# Control.net
KiCad netlist of a schematic drawn in Altium Designer
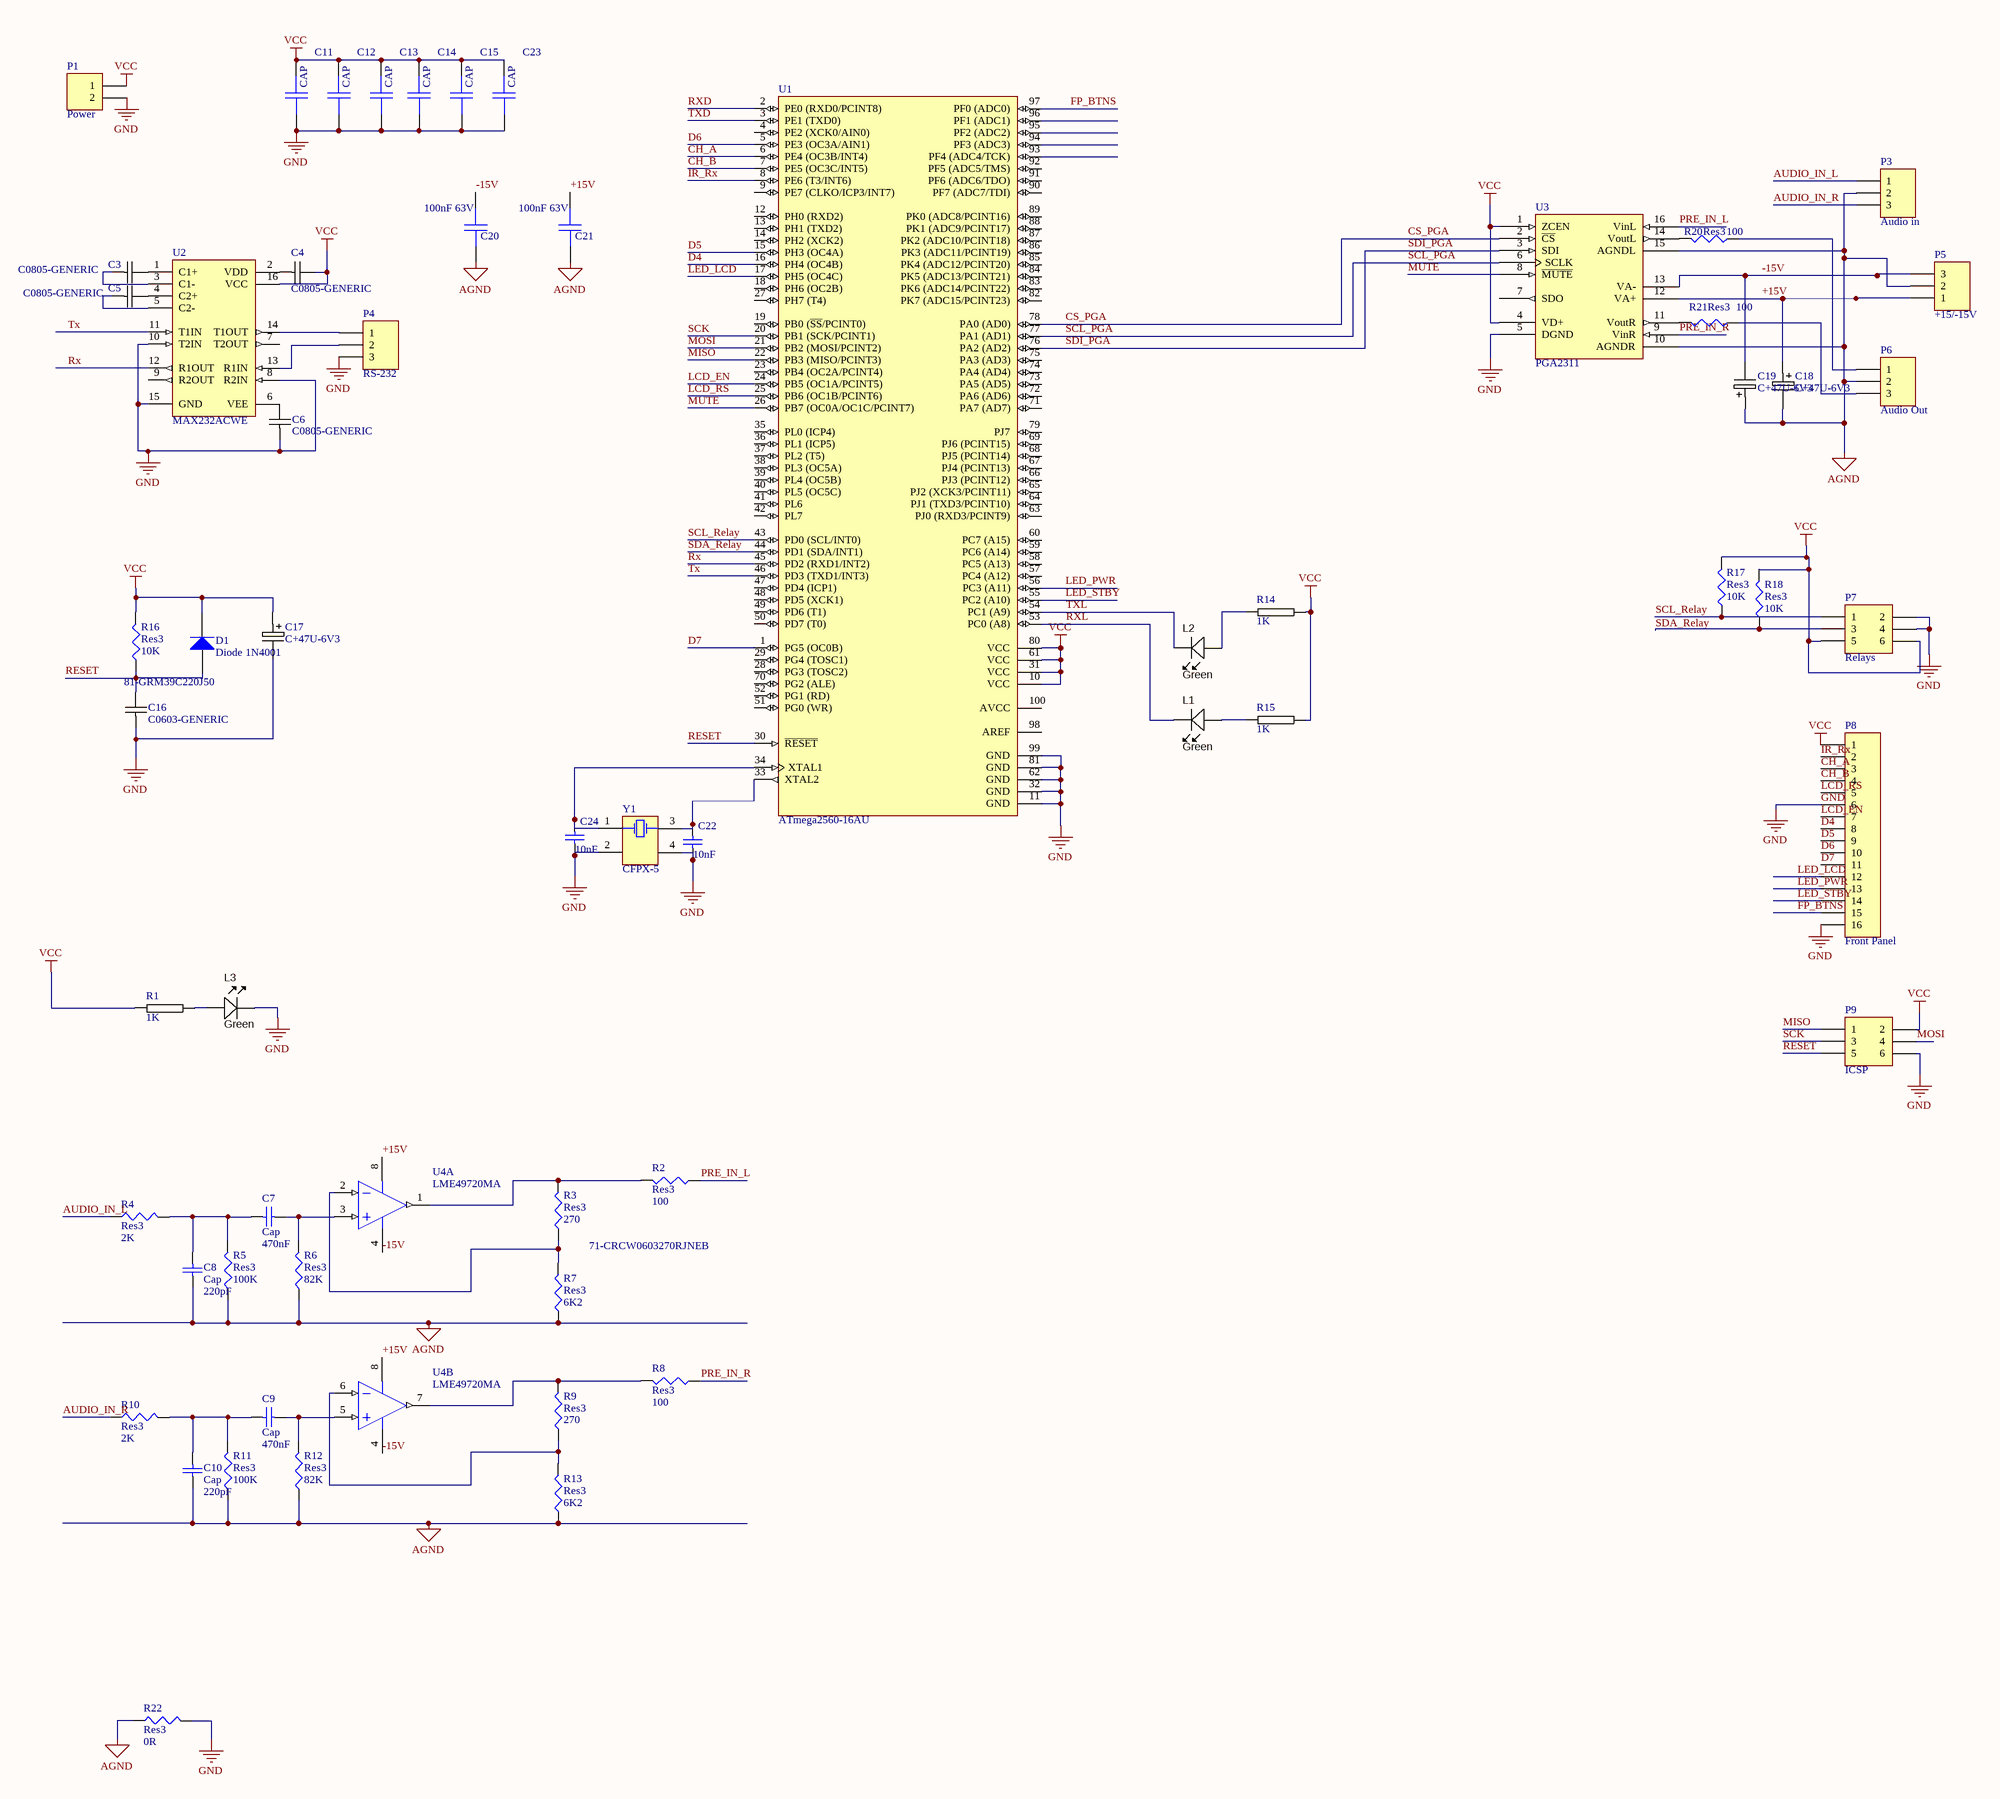
[diagram p0: Control.SchDoc]

(export (version "E")
  (design (tool "Eeschema 10.0.6"))
  (components
    (comp (ref "C3")
      (value "C0805-GENERIC")
      (footprint "0805C-GENERIC")
      (description "GENERIC CAPACITOR NON POLARISED0603")
      (libsource (lib "vh_altium_library") (part "C0805-GENERIC"))
    )
    (comp (ref "C4")
      (value "C0805-GENERIC")
      (footprint "0805C-GENERIC")
      (description "GENERIC CAPACITOR NON POLARISED0805")
      (libsource (lib "vh_altium_library") (part "C0805-GENERIC"))
    )
    (comp (ref "C5")
      (value "C0805-GENERIC")
      (footprint "0805C-GENERIC")
      (description "GENERIC CAPACITOR NON POLARISED0603")
      (libsource (lib "vh_altium_library") (part "C0805-GENERIC"))
    )
    (comp (ref "C6")
      (value "C0805-GENERIC")
      (footprint "0805C-GENERIC")
      (description "GENERIC CAPACITOR NON POLARISED0603")
      (libsource (lib "vh_altium_library") (part "C0805-GENERIC"))
    )
    (comp (ref "C7")
      (value "Cap")
      (footprint "CAPC3225X220N")
      (description "Capacitor")
      (fields (field (name "ALTIUM_VALUE") "470nF") (field (name "PUBLISHER") "Altium Limited"))
      (libsource (lib "Miscellaneous Devices") (part "Cap"))
    )
    (comp (ref "C8")
      (value "Cap")
      (footprint "CAPC2012X135N")
      (description "Capacitor")
      (fields (field (name "ALTIUM_VALUE") "220pF") (field (name "PUBLISHER") "Altium Limited"))
      (libsource (lib "Miscellaneous Devices") (part "Cap"))
    )
    (comp (ref "C9")
      (value "Cap")
      (footprint "CAPC3225X220N")
      (description "Capacitor")
      (fields (field (name "ALTIUM_VALUE") "470nF") (field (name "PUBLISHER") "Altium Limited"))
      (libsource (lib "Miscellaneous Devices") (part "Cap"))
    )
    (comp (ref "C10")
      (value "Cap")
      (footprint "CAPC2012X135N")
      (description "Capacitor")
      (fields (field (name "ALTIUM_VALUE") "220pF") (field (name "PUBLISHER") "Altium Limited"))
      (libsource (lib "Miscellaneous Devices") (part "Cap"))
    )
    (comp (ref "C11")
      (value "CAP")
      (footprint "CAPC2012")
      (description "Capacitor")
      (fields (field (name "PART NO.") "Not Part"))
      (libsource (lib "Components") (part "CAP"))
    )
    (comp (ref "C12")
      (value "CAP")
      (footprint "CAPC2012")
      (description "Capacitor")
      (fields (field (name "PART NO.") "Not Part"))
      (libsource (lib "Components") (part "CAP"))
    )
    (comp (ref "C13")
      (value "CAP")
      (footprint "CAPC2012")
      (description "Capacitor")
      (fields (field (name "PART NO.") "Not Part"))
      (libsource (lib "Components") (part "CAP"))
    )
    (comp (ref "C14")
      (value "CAP")
      (footprint "CAPC2012")
      (description "Capacitor")
      (fields (field (name "PART NO.") "Not Part"))
      (libsource (lib "Components") (part "CAP"))
    )
    (comp (ref "C15")
      (value "CAP")
      (footprint "CAPC2012")
      (description "Capacitor")
      (fields (field (name "PART NO.") "Not Part"))
      (libsource (lib "Components") (part "CAP"))
    )
    (comp (ref "C16")
      (value "C0603-GENERIC")
      (footprint "CAPC1608")
      (description "GENERIC CAPACITOR NON POLARISED 22pf")
      (fields
        (field (name "SUPPLIER PART NUMBER 1") "81-GRM39C220J50")
        (field (name "MANUFACTURER") "Murata Electronics")
        (field (name "MANUFACTURER PART NUMBER") "GRM1885C1H220JA01D")
      )
      (libsource (lib "vh_altium_library") (part "C0805-GENERIC"))
    )
    (comp (ref "C17")
      (value "C+47U-6V3")
      (footprint "PANACAP-C")
      (description "GENERIC CAPACITOR POLARISED")
      (libsource (lib "vh_altium_library") (part "C+47U-6V3"))
    )
    (comp (ref "C18")
      (value "C+47U-6V3")
      (footprint "PANACAP-C")
      (description "GENERIC CAPACITOR POLARISED")
      (libsource (lib "vh_altium_library") (part "C+47U-6V3"))
    )
    (comp (ref "C19")
      (value "C+47U-6V3")
      (footprint "PANACAP-C")
      (description "GENERIC CAPACITOR POLARISED")
      (libsource (lib "vh_altium_library") (part "C+47U-6V3"))
    )
    (comp (ref "C20")
      (value "100nF 63V")
      (footprint "CAPC3216B")
      (fields (field (name "PART NO.") "Not Part"))
      (libsource (lib "Components") (part "CAP"))
    )
    (comp (ref "C21")
      (value "100nF 63V")
      (footprint "CAPC3216B")
      (fields (field (name "PART NO.") "Not Part"))
      (libsource (lib "Components") (part "CAP"))
    )
    (comp (ref "C22")
      (value "10nF")
      (footprint "CAPC1005L")
      (description "Capacitor")
      (fields (field (name "PUBLISHER") "Altium Limited"))
      (libsource (lib "Miscellaneous Devices") (part "Cap"))
    )
    (comp (ref "C23")
      (value "CAP")
      (footprint "CAPC2012")
      (description "Capacitor")
      (fields (field (name "PART NO.") "Not Part"))
      (libsource (lib "Components") (part "CAP"))
    )
    (comp (ref "C24")
      (value "10nF")
      (footprint "CAPC1005L")
      (description "Capacitor")
      (fields (field (name "PUBLISHER") "Altium Limited"))
      (libsource (lib "Miscellaneous Devices") (part "Cap"))
    )
    (comp (ref "D1")
      (value "Diode 1N4001")
      (footprint "1206 Diode")
      (description "1 Amp General Purpose Rectifier")
      (fields (field (name "PUBLISHER") "Altium Limited"))
      (libsource (lib "Miscellaneous Devices") (part "Diode 1N4001"))
    )
    (comp (ref "L1")
      (value "~")
      (footprint "LED-0805-K")
      (description "LED, 0805 SMD, Green")
      (fields (field (name "COLOR") "Green"))
      (libsource (lib "PBL - Light Sources") (part "LED_SMD_Green_0805_6mcd"))
    )
    (comp (ref "L2")
      (value "~")
      (footprint "LED-0805-K")
      (description "LED, 0805 SMD, Green")
      (fields (field (name "COLOR") "Green"))
      (libsource (lib "PBL - Light Sources") (part "LED_SMD_Green_0805_6mcd"))
    )
    (comp (ref "L3")
      (value "~")
      (footprint "LED-0805-K")
      (description "LED, 0805 SMD, Green")
      (fields (field (name "COLOR") "Green"))
      (libsource (lib "PBL - Light Sources") (part "LED_SMD_Green_0805_6mcd"))
    )
    (comp (ref "P1")
      (value "Power")
      (footprint "PH_TERM_2")
      (description "Header, 2-Pin")
      (fields (field (name "PUBLISHER") "Altium Limited"))
      (libsource (lib "Miscellaneous Connectors") (part "Header 2"))
    )
    (comp (ref "P3")
      (value "Audio in")
      (footprint "PH_TERM_3")
      (description "Header, 3-Pin")
      (fields (field (name "PUBLISHER") "Altium Limited"))
      (libsource (lib "") (part "Header 3_1"))
    )
    (comp (ref "P4")
      (value "RS-232")
      (footprint "HDR1X3H")
      (description "Header, 3-Pin, Right Angle")
      (fields (field (name "PUBLISHER") "Altium Limited"))
      (libsource (lib "Miscellaneous Connectors") (part "Header 3H"))
    )
    (comp (ref "P5")
      (value "+15/-15V")
      (footprint "PH_TERM_3")
      (description "Header, 3-Pin")
      (fields (field (name "PUBLISHER") "Altium Limited"))
      (libsource (lib "Miscellaneous Connectors") (part "Header 3"))
    )
    (comp (ref "P6")
      (value "Audio Out")
      (footprint "PH_TERM_3")
      (description "Header, 3-Pin")
      (fields (field (name "PUBLISHER") "Altium Limited"))
      (libsource (lib "") (part "Header 3_1"))
    )
    (comp (ref "P7")
      (value "Relays")
      (footprint "HDR2X3H")
      (description "Header, 3-Pin, Dual row, Right Angle")
      (fields (field (name "PUBLISHER") "Altium Limited"))
      (libsource (lib "Miscellaneous Connectors") (part "Header 3X2H"))
    )
    (comp (ref "P8")
      (value "Front Panel")
      (footprint "IDC2.54-H16C")
      (description "Header, 16-Pin")
      (fields (field (name "PUBLISHER") "Altium Limited"))
      (libsource (lib "Miscellaneous Connectors") (part "Header 16"))
    )
    (comp (ref "P9")
      (value "ICSP")
      (footprint "HDR2X3")
      (description "Header, 3-Pin, Dual row")
      (fields (field (name "PUBLISHER") "Altium Limited"))
      (libsource (lib "Miscellaneous Connectors") (part "Header 3X2"))
    )
    (comp (ref "R1")
      (value "1K")
      (footprint "0805R-1K")
      (description "RESISTOR 0805 1/4 WATT THIN FILM")
      (libsource (lib "vh_altium_library") (part "0805R-1K"))
    )
    (comp (ref "R2")
      (value "Res3")
      (footprint "J1-0603")
      (description "Resistor")
      (fields (field (name "ALTIUM_VALUE") "100") (field (name "PUBLISHER") "Altium Limited"))
      (libsource (lib "Miscellaneous Devices") (part "Res3"))
    )
    (comp (ref "R3")
      (value "Res3")
      (footprint "J1-0603")
      (description "Resistor")
      (fields
        (field (name "ALTIUM_VALUE") "270")
        (field (name "SUPPLIER PART NUMBER 1") "71-CRCW0603270RJNEB")
        (field (name "PUBLISHER") "Altium Limited")
      )
      (libsource (lib "Miscellaneous Devices") (part "Res3"))
    )
    (comp (ref "R4")
      (value "Res3")
      (footprint "J1-0603")
      (description "Resistor")
      (fields (field (name "ALTIUM_VALUE") "2K") (field (name "PUBLISHER") "Altium Limited"))
      (libsource (lib "Miscellaneous Devices") (part "Res3"))
    )
    (comp (ref "R5")
      (value "Res3")
      (footprint "J1-0603")
      (description "Resistor")
      (fields (field (name "ALTIUM_VALUE") "100K") (field (name "PUBLISHER") "Altium Limited"))
      (libsource (lib "Miscellaneous Devices") (part "Res3"))
    )
    (comp (ref "R6")
      (value "Res3")
      (footprint "J1-0603")
      (description "Resistor")
      (fields (field (name "ALTIUM_VALUE") "82K") (field (name "PUBLISHER") "Altium Limited"))
      (libsource (lib "Miscellaneous Devices") (part "Res3"))
    )
    (comp (ref "R7")
      (value "Res3")
      (footprint "J1-0603")
      (description "Resistor")
      (fields (field (name "ALTIUM_VALUE") "6K2") (field (name "PUBLISHER") "Altium Limited"))
      (libsource (lib "Miscellaneous Devices") (part "Res3"))
    )
    (comp (ref "R8")
      (value "Res3")
      (footprint "J1-0603")
      (description "Resistor")
      (fields (field (name "ALTIUM_VALUE") "100") (field (name "PUBLISHER") "Altium Limited"))
      (libsource (lib "Miscellaneous Devices") (part "Res3"))
    )
    (comp (ref "R9")
      (value "Res3")
      (footprint "J1-0603")
      (description "Resistor")
      (fields (field (name "ALTIUM_VALUE") "270") (field (name "PUBLISHER") "Altium Limited"))
      (libsource (lib "Miscellaneous Devices") (part "Res3"))
    )
    (comp (ref "R10")
      (value "Res3")
      (footprint "J1-0603")
      (description "Resistor")
      (fields (field (name "ALTIUM_VALUE") "2K") (field (name "PUBLISHER") "Altium Limited"))
      (libsource (lib "Miscellaneous Devices") (part "Res3"))
    )
    (comp (ref "R11")
      (value "Res3")
      (footprint "J1-0603")
      (description "Resistor")
      (fields (field (name "ALTIUM_VALUE") "100K") (field (name "PUBLISHER") "Altium Limited"))
      (libsource (lib "Miscellaneous Devices") (part "Res3"))
    )
    (comp (ref "R12")
      (value "Res3")
      (footprint "J1-0603")
      (description "Resistor")
      (fields (field (name "ALTIUM_VALUE") "82K") (field (name "PUBLISHER") "Altium Limited"))
      (libsource (lib "Miscellaneous Devices") (part "Res3"))
    )
    (comp (ref "R13")
      (value "Res3")
      (footprint "J1-0603")
      (description "Resistor")
      (fields (field (name "ALTIUM_VALUE") "6K2") (field (name "PUBLISHER") "Altium Limited"))
      (libsource (lib "Miscellaneous Devices") (part "Res3"))
    )
    (comp (ref "R14")
      (value "1K")
      (footprint "0805R-1K")
      (description "RESISTOR 0805 1/4 WATT THIN FILM")
      (libsource (lib "vh_altium_library") (part "0805R-1K"))
    )
    (comp (ref "R15")
      (value "1K")
      (footprint "0805R-1K")
      (description "RESISTOR 0805 1/4 WATT THIN FILM")
      (libsource (lib "vh_altium_library") (part "0805R-1K"))
    )
    (comp (ref "R16")
      (value "Res3")
      (footprint "J1-0603")
      (description "Resistor")
      (fields (field (name "ALTIUM_VALUE") "10K") (field (name "PUBLISHER") "Altium Limited"))
      (libsource (lib "Miscellaneous Devices") (part "Res3"))
    )
    (comp (ref "R17")
      (value "Res3")
      (footprint "J1-0603")
      (description "Resistor")
      (fields (field (name "ALTIUM_VALUE") "10K") (field (name "PUBLISHER") "Altium Limited"))
      (libsource (lib "Miscellaneous Devices") (part "Res3"))
    )
    (comp (ref "R18")
      (value "Res3")
      (footprint "J1-0603")
      (description "Resistor")
      (fields (field (name "ALTIUM_VALUE") "10K") (field (name "PUBLISHER") "Altium Limited"))
      (libsource (lib "Miscellaneous Devices") (part "Res3"))
    )
    (comp (ref "R20")
      (value "Res3")
      (footprint "J1-0603")
      (description "Resistor")
      (fields (field (name "ALTIUM_VALUE") "100") (field (name "PUBLISHER") "Altium Limited"))
      (libsource (lib "Miscellaneous Devices") (part "Res3"))
    )
    (comp (ref "R21")
      (value "Res3")
      (footprint "J1-0603")
      (description "Resistor")
      (fields (field (name "ALTIUM_VALUE") "100") (field (name "PUBLISHER") "Altium Limited"))
      (libsource (lib "Miscellaneous Devices") (part "Res3"))
    )
    (comp (ref "R22")
      (value "Res3")
      (footprint "J1-0603")
      (description "Resistor")
      (fields (field (name "ALTIUM_VALUE") "0R") (field (name "PUBLISHER") "Altium Limited"))
      (libsource (lib "Miscellaneous Devices") (part "Res3"))
    )
    (comp (ref "U1")
      (value "ATmega2560-16AU")
      (footprint "100A_N")
      (fields (field (name "PUBLISHER") "Altium Limited"))
      (libsource (lib "Atmel Microcontroller 8-Bit megaAVR") (part "ATmega2560-16AU"))
    )
    (comp (ref "U2")
      (value "MAX232ACWE")
      (footprint "WSO16_N")
      (description "+5V Powered, Multi-Channel RS-232 Driver/Receiver")
      (fields (field (name "PUBLISHER") "Altium Limited"))
      (libsource (lib "Maxim Communication Transceiver") (part "MAX232ACWE"))
    )
    (comp (ref "U3")
      (value "PGA2311")
      (footprint "TI-DW16_L")
      (libsource (lib "Dales Custom Libs") (part "PGA2311"))
    )
    (comp (ref "U4")
      (value "LME49720MA")
      (footprint "M08A_N")
      (description "Dual High Performance, High Fidelity Audio Operational Amplifier, 8-pin Narrow SOIC")
      (fields
        (field (name "MANUFACTURER") "National Semiconductor")
        (field (name "PUBLISHER") "Altium Limited")
      )
      (libsource (lib "NSC Audio") (part "LME49720MA"))
    )
    (comp (ref "Y1")
      (value "CFPX-5")
      (footprint "CFPX-5")
      (description "Surface Mount Quartz Crystal")
      (fields (field (name "PUBLISHER") "Altium Limited"))
      (libsource (lib "C-MAC Crystal Oscillator") (part "CFPX-5"))
    )
  )
  (nets
    (net (code "1") (name "/+15V") (class "Default")
      (node (ref "C18") (pin "+") (pinfunction "+_+") (pintype "passive"))
      (node (ref "C21") (pin "1") (pinfunction "1_1") (pintype "passive"))
      (node (ref "P5") (pin "1") (pinfunction "1_1") (pintype "passive"))
      (node (ref "U3") (pin "12") (pinfunction "VA+_12") (pintype "power_in"))
      (node (ref "U4") (pin "8") (pinfunction "V+_8") (pintype "power_in"))
    )
    (net (code "2") (name "/-15V") (class "Default")
      (node (ref "C19") (pin "-") (pinfunction "-_-") (pintype "passive"))
      (node (ref "C20") (pin "1") (pinfunction "1_1") (pintype "passive"))
      (node (ref "P5") (pin "3") (pinfunction "3_3") (pintype "passive"))
      (node (ref "U3") (pin "13") (pinfunction "VA-_13") (pintype "power_in"))
      (node (ref "U4") (pin "4") (pinfunction "V-_4") (pintype "power_in"))
    )
    (net (code "3") (name "/AUDIO_IN_L") (class "Default")
      (node (ref "P3") (pin "1") (pinfunction "1_1") (pintype "passive"))
      (node (ref "R4") (pin "1") (pinfunction "1_1") (pintype "passive"))
    )
    (net (code "4") (name "/AUDIO_IN_R") (class "Default")
      (node (ref "P3") (pin "3") (pinfunction "3_3") (pintype "passive"))
      (node (ref "R10") (pin "1") (pinfunction "1_1") (pintype "passive"))
    )
    (net (code "5") (name "/CH_A") (class "Default")
      (node (ref "P8") (pin "3") (pinfunction "3_3") (pintype "passive"))
      (node (ref "U1") (pin "6") (pinfunction "PE4_(OC3B/INT4)_6") (pintype "bidirectional"))
    )
    (net (code "6") (name "/CH_B") (class "Default")
      (node (ref "P8") (pin "4") (pinfunction "4_4") (pintype "passive"))
      (node (ref "U1") (pin "7") (pinfunction "PE5_(OC3C/INT5)_7") (pintype "bidirectional"))
    )
    (net (code "7") (name "/CS_PGA") (class "Default")
      (node (ref "U1") (pin "78") (pinfunction "PA0_(AD0)_78") (pintype "bidirectional"))
      (node (ref "U3") (pin "2") (pinfunction "~{CS}_2") (pintype "input"))
    )
    (net (code "8") (name "/D4") (class "Default")
      (node (ref "P8") (pin "8") (pinfunction "8_8") (pintype "passive"))
      (node (ref "U1") (pin "16") (pinfunction "PH4_(OC4B)_16") (pintype "bidirectional"))
    )
    (net (code "9") (name "/D5") (class "Default")
      (node (ref "P8") (pin "9") (pinfunction "9_9") (pintype "passive"))
      (node (ref "U1") (pin "15") (pinfunction "PH3_(OC4A)_15") (pintype "bidirectional"))
    )
    (net (code "10") (name "/D6") (class "Default")
      (node (ref "P8") (pin "10") (pinfunction "10_10") (pintype "passive"))
      (node (ref "U1") (pin "5") (pinfunction "PE3_(OC3A/AIN1)_5") (pintype "bidirectional"))
    )
    (net (code "11") (name "/D7") (class "Default")
      (node (ref "P8") (pin "11") (pinfunction "11_11") (pintype "passive"))
      (node (ref "U1") (pin "1") (pinfunction "PG5_(OC0B)_1") (pintype "bidirectional"))
    )
    (net (code "12") (name "/FP_BTNS") (class "Default")
      (node (ref "P8") (pin "15") (pinfunction "15_15") (pintype "passive"))
      (node (ref "U1") (pin "97") (pinfunction "PF0_(ADC0)_97") (pintype "bidirectional"))
    )
    (net (code "13") (name "/IR_Rx") (class "Default")
      (node (ref "P8") (pin "2") (pinfunction "2_2") (pintype "passive"))
      (node (ref "U1") (pin "8") (pinfunction "PE6_(T3/INT6)_8") (pintype "bidirectional"))
    )
    (net (code "14") (name "/LCD_EN") (class "Default")
      (node (ref "P8") (pin "7") (pinfunction "7_7") (pintype "passive"))
      (node (ref "U1") (pin "24") (pinfunction "PB5_(OC1A/PCINT5)_24") (pintype "bidirectional"))
    )
    (net (code "15") (name "/LCD_RS") (class "Default")
      (node (ref "P8") (pin "5") (pinfunction "5_5") (pintype "passive"))
      (node (ref "U1") (pin "25") (pinfunction "PB6_(OC1B/PCINT6)_25") (pintype "bidirectional"))
    )
    (net (code "16") (name "/LED_LCD") (class "Default")
      (node (ref "P8") (pin "12") (pinfunction "12_12") (pintype "passive"))
      (node (ref "U1") (pin "17") (pinfunction "PH5_(OC4C)_17") (pintype "bidirectional"))
    )
    (net (code "17") (name "/LED_PWR") (class "Default")
      (node (ref "P8") (pin "13") (pinfunction "13_13") (pintype "passive"))
      (node (ref "U1") (pin "56") (pinfunction "PC3_(A11)_56") (pintype "bidirectional"))
    )
    (net (code "18") (name "/LED_STBY") (class "Default")
      (node (ref "P8") (pin "14") (pinfunction "14_14") (pintype "passive"))
      (node (ref "U1") (pin "55") (pinfunction "PC2_(A10)_55") (pintype "bidirectional"))
    )
    (net (code "19") (name "/MISO") (class "Default")
      (node (ref "P9") (pin "1") (pinfunction "1_1") (pintype "passive"))
      (node (ref "U1") (pin "22") (pinfunction "PB3_(MISO/PCINT3)_22") (pintype "bidirectional"))
    )
    (net (code "20") (name "/MOSI") (class "Default")
      (node (ref "P9") (pin "4") (pinfunction "4_4") (pintype "passive"))
      (node (ref "U1") (pin "21") (pinfunction "PB2_(MOSI/PCINT2)_21") (pintype "bidirectional"))
    )
    (net (code "21") (name "/MUTE") (class "Default")
      (node (ref "U1") (pin "26") (pinfunction "PB7_(OC0A/OC1C/PCINT7)_26") (pintype "bidirectional"))
      (node (ref "U3") (pin "8") (pinfunction "~{MUTE}_8") (pintype "input"))
    )
    (net (code "22") (name "/PRE_IN_L") (class "Default")
      (node (ref "R2") (pin "1") (pinfunction "1_1") (pintype "passive"))
      (node (ref "U3") (pin "16") (pinfunction "VinL_16") (pintype "input"))
    )
    (net (code "23") (name "/PRE_IN_R") (class "Default")
      (node (ref "R8") (pin "1") (pinfunction "1_1") (pintype "passive"))
      (node (ref "U3") (pin "9") (pinfunction "VinR_9") (pintype "input"))
    )
    (net (code "24") (name "/RESET") (class "Default")
      (node (ref "C16") (pin "2") (pintype "passive"))
      (node (ref "D1") (pin "1") (pinfunction "A_1") (pintype "passive"))
      (node (ref "P9") (pin "5") (pinfunction "5_5") (pintype "passive"))
      (node (ref "R16") (pin "1") (pinfunction "1_1") (pintype "passive"))
      (node (ref "U1") (pin "30") (pinfunction "~{RESET}_30") (pintype "input"))
    )
    (net (code "25") (name "/RXD") (class "Default")
      (node (ref "U1") (pin "2") (pinfunction "PE0_(RXD0/PCINT8)_2") (pintype "bidirectional"))
    )
    (net (code "26") (name "/RXL") (class "Default")
      (node (ref "L1") (pin "K") (pinfunction "K_K") (pintype "passive"))
      (node (ref "U1") (pin "53") (pinfunction "PC0_(A8)_53") (pintype "bidirectional"))
    )
    (net (code "27") (name "/Rx") (class "Default")
      (node (ref "U1") (pin "45") (pinfunction "PD2_(RXD1/INT2)_45") (pintype "bidirectional"))
      (node (ref "U2") (pin "12") (pinfunction "R1OUT_12") (pintype "output"))
    )
    (net (code "28") (name "/SCK") (class "Default")
      (node (ref "P9") (pin "3") (pinfunction "3_3") (pintype "passive"))
      (node (ref "U1") (pin "20") (pinfunction "PB1_(SCK/PCINT1)_20") (pintype "bidirectional"))
    )
    (net (code "29") (name "/SCL_PGA") (class "Default")
      (node (ref "U1") (pin "77") (pinfunction "PA1_(AD1)_77") (pintype "bidirectional"))
      (node (ref "U3") (pin "6") (pinfunction "SCLK_6") (pintype "passive"))
    )
    (net (code "30") (name "/SCL_Relay") (class "Default")
      (node (ref "P7") (pin "1") (pinfunction "1_1") (pintype "passive"))
      (node (ref "R17") (pin "1") (pinfunction "1_1") (pintype "passive"))
      (node (ref "U1") (pin "43") (pinfunction "PD0_(SCL/INT0)_43") (pintype "bidirectional"))
    )
    (net (code "31") (name "/SDA_Relay") (class "Default")
      (node (ref "P7") (pin "3") (pinfunction "3_3") (pintype "passive"))
      (node (ref "R18") (pin "1") (pinfunction "1_1") (pintype "passive"))
      (node (ref "U1") (pin "44") (pinfunction "PD1_(SDA/INT1)_44") (pintype "bidirectional"))
    )
    (net (code "32") (name "/SDI_PGA") (class "Default")
      (node (ref "U1") (pin "76") (pinfunction "PA2_(AD2)_76") (pintype "bidirectional"))
      (node (ref "U3") (pin "3") (pinfunction "SDI_3") (pintype "input"))
    )
    (net (code "33") (name "/TXD") (class "Default")
      (node (ref "U1") (pin "3") (pinfunction "PE1_(TXD0)_3") (pintype "bidirectional"))
    )
    (net (code "34") (name "/TXL") (class "Default")
      (node (ref "L2") (pin "K") (pinfunction "K_K") (pintype "passive"))
      (node (ref "U1") (pin "54") (pinfunction "PC1_(A9)_54") (pintype "bidirectional"))
    )
    (net (code "35") (name "/Tx") (class "Default")
      (node (ref "U1") (pin "46") (pinfunction "PD3_(TXD1/INT3)_46") (pintype "bidirectional"))
      (node (ref "U2") (pin "11") (pinfunction "T1IN_11") (pintype "input"))
    )
    (net (code "36") (name "AGND") (class "Default")
      (node (ref "C10") (pin "2") (pinfunction "2_2") (pintype "passive"))
      (node (ref "C18") (pin "-") (pinfunction "-_-") (pintype "passive"))
      (node (ref "C19") (pin "+") (pinfunction "+_+") (pintype "passive"))
      (node (ref "C20") (pin "2") (pinfunction "2_2") (pintype "passive"))
      (node (ref "C21") (pin "2") (pinfunction "2_2") (pintype "passive"))
      (node (ref "C8") (pin "1") (pinfunction "1_1") (pintype "passive"))
      (node (ref "P3") (pin "2") (pinfunction "2_2") (pintype "passive"))
      (node (ref "P5") (pin "2") (pinfunction "2_2") (pintype "passive"))
      (node (ref "P6") (pin "2") (pinfunction "2_2") (pintype "passive"))
      (node (ref "R11") (pin "1") (pinfunction "1_1") (pintype "passive"))
      (node (ref "R12") (pin "1") (pinfunction "1_1") (pintype "passive"))
      (node (ref "R13") (pin "1") (pinfunction "1_1") (pintype "passive"))
      (node (ref "R22") (pin "1") (pinfunction "1_1") (pintype "passive"))
      (node (ref "R5") (pin "1") (pinfunction "1_1") (pintype "passive"))
      (node (ref "R6") (pin "1") (pinfunction "1_1") (pintype "passive"))
      (node (ref "R7") (pin "1") (pinfunction "1_1") (pintype "passive"))
      (node (ref "U3") (pin "10") (pinfunction "AGNDR_10") (pintype "power_in"))
      (node (ref "U3") (pin "15") (pinfunction "AGNDL_15") (pintype "power_in"))
    )
    (net (code "37") (name "GND") (class "Default")
      (node (ref "C11") (pin "2") (pinfunction "2_2") (pintype "passive"))
      (node (ref "C12") (pin "2") (pinfunction "2_2") (pintype "passive"))
      (node (ref "C13") (pin "2") (pinfunction "2_2") (pintype "passive"))
      (node (ref "C14") (pin "2") (pinfunction "2_2") (pintype "passive"))
      (node (ref "C15") (pin "2") (pinfunction "2_2") (pintype "passive"))
      (node (ref "C16") (pin "1") (pintype "passive"))
      (node (ref "C17") (pin "-") (pinfunction "-_-") (pintype "passive"))
      (node (ref "C22") (pin "1") (pinfunction "1_1") (pintype "passive"))
      (node (ref "C23") (pin "2") (pinfunction "2_2") (pintype "passive"))
      (node (ref "C24") (pin "1") (pinfunction "1_1") (pintype "passive"))
      (node (ref "C6") (pin "1") (pintype "passive"))
      (node (ref "L3") (pin "K") (pinfunction "K_K") (pintype "passive"))
      (node (ref "P1") (pin "2") (pinfunction "2_2") (pintype "passive"))
      (node (ref "P4") (pin "3") (pinfunction "3_3") (pintype "passive"))
      (node (ref "P7") (pin "2") (pinfunction "2_2") (pintype "passive"))
      (node (ref "P7") (pin "4") (pinfunction "4_4") (pintype "passive"))
      (node (ref "P8") (pin "16") (pinfunction "16_16") (pintype "passive"))
      (node (ref "P8") (pin "6") (pinfunction "6_6") (pintype "passive"))
      (node (ref "P9") (pin "6") (pinfunction "6_6") (pintype "passive"))
      (node (ref "R22") (pin "2") (pinfunction "2_2") (pintype "passive"))
      (node (ref "U1") (pin "11") (pinfunction "GND_11") (pintype "power_in"))
      (node (ref "U1") (pin "32") (pinfunction "GND_32") (pintype "power_in"))
      (node (ref "U1") (pin "62") (pinfunction "GND_62") (pintype "power_in"))
      (node (ref "U1") (pin "81") (pinfunction "GND_81") (pintype "power_in"))
      (node (ref "U1") (pin "99") (pinfunction "GND_99") (pintype "power_in"))
      (node (ref "U2") (pin "10") (pinfunction "T2IN_10") (pintype "input"))
      (node (ref "U2") (pin "15") (pinfunction "GND_15") (pintype "power_in"))
      (node (ref "U2") (pin "8") (pinfunction "R2IN_8") (pintype "input"))
      (node (ref "U3") (pin "5") (pinfunction "DGND_5") (pintype "power_in"))
      (node (ref "Y1") (pin "2") (pinfunction "NC_2") (pintype "passive"))
      (node (ref "Y1") (pin "4") (pinfunction "NC_4") (pintype "passive"))
    )
    (net (code "38") (name "Net-(C7-Pad1)") (class "Default")
      (node (ref "C7") (pin "1") (pinfunction "1_1") (pintype "passive"))
      (node (ref "R6") (pin "2") (pinfunction "2_2") (pintype "passive"))
      (node (ref "U4") (pin "3") (pinfunction "IN_A_3") (pintype "input"))
    )
    (net (code "39") (name "Net-(C7-Pad2)") (class "Default")
      (node (ref "C7") (pin "2") (pinfunction "2_2") (pintype "passive"))
      (node (ref "C8") (pin "2") (pinfunction "2_2") (pintype "passive"))
      (node (ref "R4") (pin "2") (pinfunction "2_2") (pintype "passive"))
      (node (ref "R5") (pin "2") (pinfunction "2_2") (pintype "passive"))
    )
    (net (code "40") (name "Net-(C9-Pad2)") (class "Default")
      (node (ref "C9") (pin "2") (pinfunction "2_2") (pintype "passive"))
      (node (ref "R12") (pin "2") (pinfunction "2_2") (pintype "passive"))
      (node (ref "U4") (pin "5") (pinfunction "IN_B_5") (pintype "input"))
    )
    (net (code "41") (name "Net-(C10-Pad1)") (class "Default")
      (node (ref "C10") (pin "1") (pinfunction "1_1") (pintype "passive"))
      (node (ref "C9") (pin "1") (pinfunction "1_1") (pintype "passive"))
      (node (ref "R10") (pin "2") (pinfunction "2_2") (pintype "passive"))
      (node (ref "R11") (pin "2") (pinfunction "2_2") (pintype "passive"))
    )
    (net (code "42") (name "Net-(L1-PadA)") (class "Default")
      (node (ref "L1") (pin "A") (pinfunction "A_A") (pintype "passive"))
      (node (ref "R15") (pin "1") (pintype "passive"))
    )
    (net (code "43") (name "Net-(L2-PadA)") (class "Default")
      (node (ref "L2") (pin "A") (pinfunction "A_A") (pintype "passive"))
      (node (ref "R14") (pin "1") (pintype "passive"))
    )
    (net (code "44") (name "Net-(L3-PadA)") (class "Default")
      (node (ref "L3") (pin "A") (pinfunction "A_A") (pintype "passive"))
      (node (ref "R1") (pin "2") (pintype "passive"))
    )
    (net (code "45") (name "Net-(P6-Pad1)") (class "Default")
      (node (ref "P6") (pin "1") (pinfunction "1_1") (pintype "passive"))
      (node (ref "R20") (pin "1") (pinfunction "1_1") (pintype "passive"))
    )
    (net (code "46") (name "Net-(P6-Pad3)") (class "Default")
      (node (ref "P6") (pin "3") (pinfunction "3_3") (pintype "passive"))
      (node (ref "R21") (pin "1") (pinfunction "1_1") (pintype "passive"))
    )
    (net (code "47") (name "Net-(R3-Pad1)") (class "Default")
      (node (ref "R3") (pin "1") (pinfunction "1_1") (pintype "passive"))
      (node (ref "R7") (pin "2") (pinfunction "2_2") (pintype "passive"))
      (node (ref "U4") (pin "2") (pinfunction "IN_A_2") (pintype "input"))
    )
    (net (code "48") (name "Net-(R13-Pad2)") (class "Default")
      (node (ref "R13") (pin "2") (pinfunction "2_2") (pintype "passive"))
      (node (ref "R9") (pin "1") (pinfunction "1_1") (pintype "passive"))
      (node (ref "U4") (pin "6") (pinfunction "IN_B_6") (pintype "input"))
    )
    (net (code "49") (name "Net-(U1-XTAL1)") (class "Default")
      (node (ref "C24") (pin "2") (pinfunction "2_2") (pintype "passive"))
      (node (ref "U1") (pin "34") (pinfunction "XTAL1_34") (pintype "input"))
      (node (ref "Y1") (pin "1") (pinfunction "OSC1_1") (pintype "passive"))
    )
    (net (code "50") (name "Net-(U1-XTAL2)") (class "Default")
      (node (ref "C22") (pin "2") (pinfunction "2_2") (pintype "passive"))
      (node (ref "U1") (pin "33") (pinfunction "XTAL2_33") (pintype "output"))
      (node (ref "Y1") (pin "3") (pinfunction "OSC2_3") (pintype "passive"))
    )
    (net (code "51") (name "Net-(U2-C1+)") (class "Default")
      (node (ref "C3") (pin "2") (pintype "passive"))
      (node (ref "U2") (pin "1") (pinfunction "C1+_1") (pintype "passive"))
    )
    (net (code "52") (name "Net-(U2-C1-)") (class "Default")
      (node (ref "C3") (pin "1") (pintype "passive"))
      (node (ref "U2") (pin "3") (pinfunction "C1-_3") (pintype "passive"))
    )
    (net (code "53") (name "Net-(U2-C2+)") (class "Default")
      (node (ref "C5") (pin "2") (pintype "passive"))
      (node (ref "U2") (pin "4") (pinfunction "C2+_4") (pintype "passive"))
    )
    (net (code "54") (name "Net-(U2-C2-)") (class "Default")
      (node (ref "C5") (pin "1") (pintype "passive"))
      (node (ref "U2") (pin "5") (pinfunction "C2-_5") (pintype "passive"))
    )
    (net (code "55") (name "Net-(U2-R1IN)") (class "Default")
      (node (ref "P4") (pin "2") (pinfunction "2_2") (pintype "passive"))
      (node (ref "U2") (pin "13") (pinfunction "R1IN_13") (pintype "input"))
    )
    (net (code "56") (name "Net-(U2-T1OUT)") (class "Default")
      (node (ref "P4") (pin "1") (pinfunction "1_1") (pintype "passive"))
      (node (ref "U2") (pin "14") (pinfunction "T1OUT_14") (pintype "output"))
    )
    (net (code "57") (name "Net-(U2-VDD)") (class "Default")
      (node (ref "C4") (pin "1") (pintype "passive"))
      (node (ref "U2") (pin "2") (pinfunction "VDD_2") (pintype "power_in"))
    )
    (net (code "58") (name "Net-(U2-VEE)") (class "Default")
      (node (ref "C6") (pin "2") (pintype "passive"))
      (node (ref "U2") (pin "6") (pinfunction "VEE_6") (pintype "power_in"))
    )
    (net (code "59") (name "Net-(U3-VoutL)") (class "Default")
      (node (ref "R20") (pin "2") (pinfunction "2_2") (pintype "passive"))
      (node (ref "U3") (pin "14") (pinfunction "VoutL_14") (pintype "output"))
    )
    (net (code "60") (name "Net-(U3-VoutR)") (class "Default")
      (node (ref "R21") (pin "2") (pinfunction "2_2") (pintype "passive"))
      (node (ref "U3") (pin "11") (pinfunction "VoutR_11") (pintype "output"))
    )
    (net (code "61") (name "Net-(U4A-OUT_A)") (class "Default")
      (node (ref "R2") (pin "2") (pinfunction "2_2") (pintype "passive"))
      (node (ref "R3") (pin "2") (pinfunction "2_2") (pintype "passive"))
      (node (ref "U4") (pin "1") (pinfunction "OUT_A_1") (pintype "output"))
    )
    (net (code "62") (name "Net-(U4B-OUT_B)") (class "Default")
      (node (ref "R8") (pin "2") (pinfunction "2_2") (pintype "passive"))
      (node (ref "R9") (pin "2") (pinfunction "2_2") (pintype "passive"))
      (node (ref "U4") (pin "7") (pinfunction "OUT_B_7") (pintype "output"))
    )
    (net (code "63") (name "VCC") (class "Default")
      (node (ref "C11") (pin "1") (pinfunction "1_1") (pintype "passive"))
      (node (ref "C12") (pin "1") (pinfunction "1_1") (pintype "passive"))
      (node (ref "C13") (pin "1") (pinfunction "1_1") (pintype "passive"))
      (node (ref "C14") (pin "1") (pinfunction "1_1") (pintype "passive"))
      (node (ref "C15") (pin "1") (pinfunction "1_1") (pintype "passive"))
      (node (ref "C17") (pin "+") (pinfunction "+_+") (pintype "passive"))
      (node (ref "C23") (pin "1") (pinfunction "1_1") (pintype "passive"))
      (node (ref "C4") (pin "2") (pintype "passive"))
      (node (ref "D1") (pin "2") (pinfunction "K_2") (pintype "passive"))
      (node (ref "P1") (pin "1") (pinfunction "1_1") (pintype "passive"))
      (node (ref "P7") (pin "5") (pinfunction "5_5") (pintype "passive"))
      (node (ref "P7") (pin "6") (pinfunction "6_6") (pintype "passive"))
      (node (ref "P8") (pin "1") (pinfunction "1_1") (pintype "passive"))
      (node (ref "P9") (pin "2") (pinfunction "2_2") (pintype "passive"))
      (node (ref "R1") (pin "1") (pintype "passive"))
      (node (ref "R14") (pin "2") (pintype "passive"))
      (node (ref "R15") (pin "2") (pintype "passive"))
      (node (ref "R16") (pin "2") (pinfunction "2_2") (pintype "passive"))
      (node (ref "R17") (pin "2") (pinfunction "2_2") (pintype "passive"))
      (node (ref "R18") (pin "2") (pinfunction "2_2") (pintype "passive"))
      (node (ref "U1") (pin "10") (pinfunction "VCC_10") (pintype "power_in"))
      (node (ref "U1") (pin "31") (pinfunction "VCC_31") (pintype "power_in"))
      (node (ref "U1") (pin "61") (pinfunction "VCC_61") (pintype "power_in"))
      (node (ref "U1") (pin "80") (pinfunction "VCC_80") (pintype "power_in"))
      (node (ref "U2") (pin "16") (pinfunction "VCC_16") (pintype "power_in"))
      (node (ref "U3") (pin "1") (pinfunction "ZCEN_1") (pintype "input"))
      (node (ref "U3") (pin "4") (pinfunction "VD+_4") (pintype "power_in"))
    )
    (net (code "64") (name "unconnected-(U1-AREF-Pad98)") (class "Default")
      (node (ref "U1") (pin "98") (pinfunction "AREF_98") (pintype "power_in"))
    )
    (net (code "65") (name "unconnected-(U1-AVCC-Pad100)") (class "Default")
      (node (ref "U1") (pin "100") (pinfunction "AVCC_100") (pintype "power_in"))
    )
    (net (code "66") (name "unconnected-(U1-PA3_(AD3)-Pad75)") (class "Default")
      (node (ref "U1") (pin "75") (pinfunction "PA3_(AD3)_75") (pintype "bidirectional"))
    )
    (net (code "67") (name "unconnected-(U1-PA4_(AD4)-Pad74)") (class "Default")
      (node (ref "U1") (pin "74") (pinfunction "PA4_(AD4)_74") (pintype "bidirectional"))
    )
    (net (code "68") (name "unconnected-(U1-PA5_(AD5)-Pad73)") (class "Default")
      (node (ref "U1") (pin "73") (pinfunction "PA5_(AD5)_73") (pintype "bidirectional"))
    )
    (net (code "69") (name "unconnected-(U1-PA6_(AD6)-Pad72)") (class "Default")
      (node (ref "U1") (pin "72") (pinfunction "PA6_(AD6)_72") (pintype "bidirectional"))
    )
    (net (code "70") (name "unconnected-(U1-PA7_(AD7)-Pad71)") (class "Default")
      (node (ref "U1") (pin "71") (pinfunction "PA7_(AD7)_71") (pintype "bidirectional"))
    )
    (net (code "71") (name "unconnected-(U1-PB0_(~{SS}{slash}PCINT0)-Pad19)") (class "Default")
      (node (ref "U1") (pin "19") (pinfunction "PB0_(~{SS}/PCINT0)_19") (pintype "bidirectional"))
    )
    (net (code "72") (name "unconnected-(U1-PB4_(OC2A{slash}PCINT4)-Pad23)") (class "Default")
      (node (ref "U1") (pin "23") (pinfunction "PB4_(OC2A/PCINT4)_23") (pintype "bidirectional"))
    )
    (net (code "73") (name "unconnected-(U1-PC4_(A12)-Pad57)") (class "Default")
      (node (ref "U1") (pin "57") (pinfunction "PC4_(A12)_57") (pintype "bidirectional"))
    )
    (net (code "74") (name "unconnected-(U1-PC5_(A13)-Pad58)") (class "Default")
      (node (ref "U1") (pin "58") (pinfunction "PC5_(A13)_58") (pintype "bidirectional"))
    )
    (net (code "75") (name "unconnected-(U1-PC6_(A14)-Pad59)") (class "Default")
      (node (ref "U1") (pin "59") (pinfunction "PC6_(A14)_59") (pintype "bidirectional"))
    )
    (net (code "76") (name "unconnected-(U1-PC7_(A15)-Pad60)") (class "Default")
      (node (ref "U1") (pin "60") (pinfunction "PC7_(A15)_60") (pintype "bidirectional"))
    )
    (net (code "77") (name "unconnected-(U1-PD4_(ICP1)-Pad47)") (class "Default")
      (node (ref "U1") (pin "47") (pinfunction "PD4_(ICP1)_47") (pintype "bidirectional"))
    )
    (net (code "78") (name "unconnected-(U1-PD5_(XCK1)-Pad48)") (class "Default")
      (node (ref "U1") (pin "48") (pinfunction "PD5_(XCK1)_48") (pintype "bidirectional"))
    )
    (net (code "79") (name "unconnected-(U1-PD6_(T1)-Pad49)") (class "Default")
      (node (ref "U1") (pin "49") (pinfunction "PD6_(T1)_49") (pintype "bidirectional"))
    )
    (net (code "80") (name "unconnected-(U1-PD7_(T0)-Pad50)") (class "Default")
      (node (ref "U1") (pin "50") (pinfunction "PD7_(T0)_50") (pintype "bidirectional"))
    )
    (net (code "81") (name "unconnected-(U1-PE2_(XCK0{slash}AIN0)-Pad4)") (class "Default")
      (node (ref "U1") (pin "4") (pinfunction "PE2_(XCK0/AIN0)_4") (pintype "bidirectional"))
    )
    (net (code "82") (name "unconnected-(U1-PE7_(CLKO{slash}ICP3{slash}INT7)-Pad9)") (class "Default")
      (node (ref "U1") (pin "9") (pinfunction "PE7_(CLKO/ICP3/INT7)_9") (pintype "bidirectional"))
    )
    (net (code "83") (name "unconnected-(U1-PF1_(ADC1)-Pad96)") (class "Default")
      (node (ref "U1") (pin "96") (pinfunction "PF1_(ADC1)_96") (pintype "bidirectional"))
    )
    (net (code "84") (name "unconnected-(U1-PF2_(ADC2)-Pad95)") (class "Default")
      (node (ref "U1") (pin "95") (pinfunction "PF2_(ADC2)_95") (pintype "bidirectional"))
    )
    (net (code "85") (name "unconnected-(U1-PF3_(ADC3)-Pad94)") (class "Default")
      (node (ref "U1") (pin "94") (pinfunction "PF3_(ADC3)_94") (pintype "bidirectional"))
    )
    (net (code "86") (name "unconnected-(U1-PF4_(ADC4{slash}TCK)-Pad93)") (class "Default")
      (node (ref "U1") (pin "93") (pinfunction "PF4_(ADC4/TCK)_93") (pintype "bidirectional"))
    )
    (net (code "87") (name "unconnected-(U1-PF5_(ADC5{slash}TMS)-Pad92)") (class "Default")
      (node (ref "U1") (pin "92") (pinfunction "PF5_(ADC5/TMS)_92") (pintype "bidirectional"))
    )
    (net (code "88") (name "unconnected-(U1-PF6_(ADC6{slash}TDO)-Pad91)") (class "Default")
      (node (ref "U1") (pin "91") (pinfunction "PF6_(ADC6/TDO)_91") (pintype "bidirectional"))
    )
    (net (code "89") (name "unconnected-(U1-PF7_(ADC7{slash}TDI)-Pad90)") (class "Default")
      (node (ref "U1") (pin "90") (pinfunction "PF7_(ADC7/TDI)_90") (pintype "bidirectional"))
    )
    (net (code "90") (name "unconnected-(U1-PG0_(WR)-Pad51)") (class "Default")
      (node (ref "U1") (pin "51") (pinfunction "PG0_(WR)_51") (pintype "bidirectional"))
    )
    (net (code "91") (name "unconnected-(U1-PG1_(RD)-Pad52)") (class "Default")
      (node (ref "U1") (pin "52") (pinfunction "PG1_(RD)_52") (pintype "bidirectional"))
    )
    (net (code "92") (name "unconnected-(U1-PG2_(ALE)-Pad70)") (class "Default")
      (node (ref "U1") (pin "70") (pinfunction "PG2_(ALE)_70") (pintype "bidirectional"))
    )
    (net (code "93") (name "unconnected-(U1-PG3_(TOSC2)-Pad28)") (class "Default")
      (node (ref "U1") (pin "28") (pinfunction "PG3_(TOSC2)_28") (pintype "bidirectional"))
    )
    (net (code "94") (name "unconnected-(U1-PG4_(TOSC1)-Pad29)") (class "Default")
      (node (ref "U1") (pin "29") (pinfunction "PG4_(TOSC1)_29") (pintype "bidirectional"))
    )
    (net (code "95") (name "unconnected-(U1-PH0_(RXD2)-Pad12)") (class "Default")
      (node (ref "U1") (pin "12") (pinfunction "PH0_(RXD2)_12") (pintype "bidirectional"))
    )
    (net (code "96") (name "unconnected-(U1-PH1_(TXD2)-Pad13)") (class "Default")
      (node (ref "U1") (pin "13") (pinfunction "PH1_(TXD2)_13") (pintype "bidirectional"))
    )
    (net (code "97") (name "unconnected-(U1-PH2_(XCK2)-Pad14)") (class "Default")
      (node (ref "U1") (pin "14") (pinfunction "PH2_(XCK2)_14") (pintype "bidirectional"))
    )
    (net (code "98") (name "unconnected-(U1-PH6_(OC2B)-Pad18)") (class "Default")
      (node (ref "U1") (pin "18") (pinfunction "PH6_(OC2B)_18") (pintype "bidirectional"))
    )
    (net (code "99") (name "unconnected-(U1-PH7_(T4)-Pad27)") (class "Default")
      (node (ref "U1") (pin "27") (pinfunction "PH7_(T4)_27") (pintype "bidirectional"))
    )
    (net (code "100") (name "unconnected-(U1-PJ0_(RXD3{slash}PCINT9)-Pad63)") (class "Default")
      (node (ref "U1") (pin "63") (pinfunction "PJ0_(RXD3/PCINT9)_63") (pintype "bidirectional"))
    )
    (net (code "101") (name "unconnected-(U1-PJ1_(TXD3{slash}PCINT10)-Pad64)") (class "Default")
      (node (ref "U1") (pin "64") (pinfunction "PJ1_(TXD3/PCINT10)_64") (pintype "bidirectional"))
    )
    (net (code "102") (name "unconnected-(U1-PJ2_(XCK3{slash}PCINT11)-Pad65)") (class "Default")
      (node (ref "U1") (pin "65") (pinfunction "PJ2_(XCK3/PCINT11)_65") (pintype "bidirectional"))
    )
    (net (code "103") (name "unconnected-(U1-PJ3_(PCINT12)-Pad66)") (class "Default")
      (node (ref "U1") (pin "66") (pinfunction "PJ3_(PCINT12)_66") (pintype "bidirectional"))
    )
    (net (code "104") (name "unconnected-(U1-PJ4_(PCINT13)-Pad67)") (class "Default")
      (node (ref "U1") (pin "67") (pinfunction "PJ4_(PCINT13)_67") (pintype "bidirectional"))
    )
    (net (code "105") (name "unconnected-(U1-PJ5_(PCINT14)-Pad68)") (class "Default")
      (node (ref "U1") (pin "68") (pinfunction "PJ5_(PCINT14)_68") (pintype "bidirectional"))
    )
    (net (code "106") (name "unconnected-(U1-PJ6_(PCINT15)-Pad69)") (class "Default")
      (node (ref "U1") (pin "69") (pinfunction "PJ6_(PCINT15)_69") (pintype "bidirectional"))
    )
    (net (code "107") (name "unconnected-(U1-PJ7-Pad79)") (class "Default")
      (node (ref "U1") (pin "79") (pinfunction "PJ7_79") (pintype "bidirectional"))
    )
    (net (code "108") (name "unconnected-(U1-PK0_(ADC8{slash}PCINT16)-Pad89)") (class "Default")
      (node (ref "U1") (pin "89") (pinfunction "PK0_(ADC8/PCINT16)_89") (pintype "bidirectional"))
    )
    (net (code "109") (name "unconnected-(U1-PK1_(ADC9{slash}PCINT17)-Pad88)") (class "Default")
      (node (ref "U1") (pin "88") (pinfunction "PK1_(ADC9/PCINT17)_88") (pintype "bidirectional"))
    )
    (net (code "110") (name "unconnected-(U1-PK2_(ADC10{slash}PCINT18)-Pad87)") (class "Default")
      (node (ref "U1") (pin "87") (pinfunction "PK2_(ADC10/PCINT18)_87") (pintype "bidirectional"))
    )
    (net (code "111") (name "unconnected-(U1-PK3_(ADC11{slash}PCINT19)-Pad86)") (class "Default")
      (node (ref "U1") (pin "86") (pinfunction "PK3_(ADC11/PCINT19)_86") (pintype "bidirectional"))
    )
    (net (code "112") (name "unconnected-(U1-PK4_(ADC12{slash}PCINT20)-Pad85)") (class "Default")
      (node (ref "U1") (pin "85") (pinfunction "PK4_(ADC12/PCINT20)_85") (pintype "bidirectional"))
    )
    (net (code "113") (name "unconnected-(U1-PK5_(ADC13{slash}PCINT21)-Pad84)") (class "Default")
      (node (ref "U1") (pin "84") (pinfunction "PK5_(ADC13/PCINT21)_84") (pintype "bidirectional"))
    )
    (net (code "114") (name "unconnected-(U1-PK6_(ADC14{slash}PCINT22)-Pad83)") (class "Default")
      (node (ref "U1") (pin "83") (pinfunction "PK6_(ADC14/PCINT22)_83") (pintype "bidirectional"))
    )
    (net (code "115") (name "unconnected-(U1-PK7_(ADC15{slash}PCINT23)-Pad82)") (class "Default")
      (node (ref "U1") (pin "82") (pinfunction "PK7_(ADC15/PCINT23)_82") (pintype "bidirectional"))
    )
    (net (code "116") (name "unconnected-(U1-PL0_(ICP4)-Pad35)") (class "Default")
      (node (ref "U1") (pin "35") (pinfunction "PL0_(ICP4)_35") (pintype "bidirectional"))
    )
    (net (code "117") (name "unconnected-(U1-PL1_(ICP5)-Pad36)") (class "Default")
      (node (ref "U1") (pin "36") (pinfunction "PL1_(ICP5)_36") (pintype "bidirectional"))
    )
    (net (code "118") (name "unconnected-(U1-PL2_(T5)-Pad37)") (class "Default")
      (node (ref "U1") (pin "37") (pinfunction "PL2_(T5)_37") (pintype "bidirectional"))
    )
    (net (code "119") (name "unconnected-(U1-PL3_(OC5A)-Pad38)") (class "Default")
      (node (ref "U1") (pin "38") (pinfunction "PL3_(OC5A)_38") (pintype "bidirectional"))
    )
    (net (code "120") (name "unconnected-(U1-PL4_(OC5B)-Pad39)") (class "Default")
      (node (ref "U1") (pin "39") (pinfunction "PL4_(OC5B)_39") (pintype "bidirectional"))
    )
    (net (code "121") (name "unconnected-(U1-PL5_(OC5C)-Pad40)") (class "Default")
      (node (ref "U1") (pin "40") (pinfunction "PL5_(OC5C)_40") (pintype "bidirectional"))
    )
    (net (code "122") (name "unconnected-(U1-PL6-Pad41)") (class "Default")
      (node (ref "U1") (pin "41") (pinfunction "PL6_41") (pintype "bidirectional"))
    )
    (net (code "123") (name "unconnected-(U1-PL7-Pad42)") (class "Default")
      (node (ref "U1") (pin "42") (pinfunction "PL7_42") (pintype "bidirectional"))
    )
    (net (code "124") (name "unconnected-(U2-R2OUT-Pad9)") (class "Default")
      (node (ref "U2") (pin "9") (pinfunction "R2OUT_9") (pintype "output"))
    )
    (net (code "125") (name "unconnected-(U2-T2OUT-Pad7)") (class "Default")
      (node (ref "U2") (pin "7") (pinfunction "T2OUT_7") (pintype "output"))
    )
    (net (code "126") (name "unconnected-(U3-SDO-Pad7)") (class "Default")
      (node (ref "U3") (pin "7") (pinfunction "SDO_7") (pintype "output"))
    )
  )
)
